# MAIN.net
KiCad netlist of a schematic drawn in Altium Designer
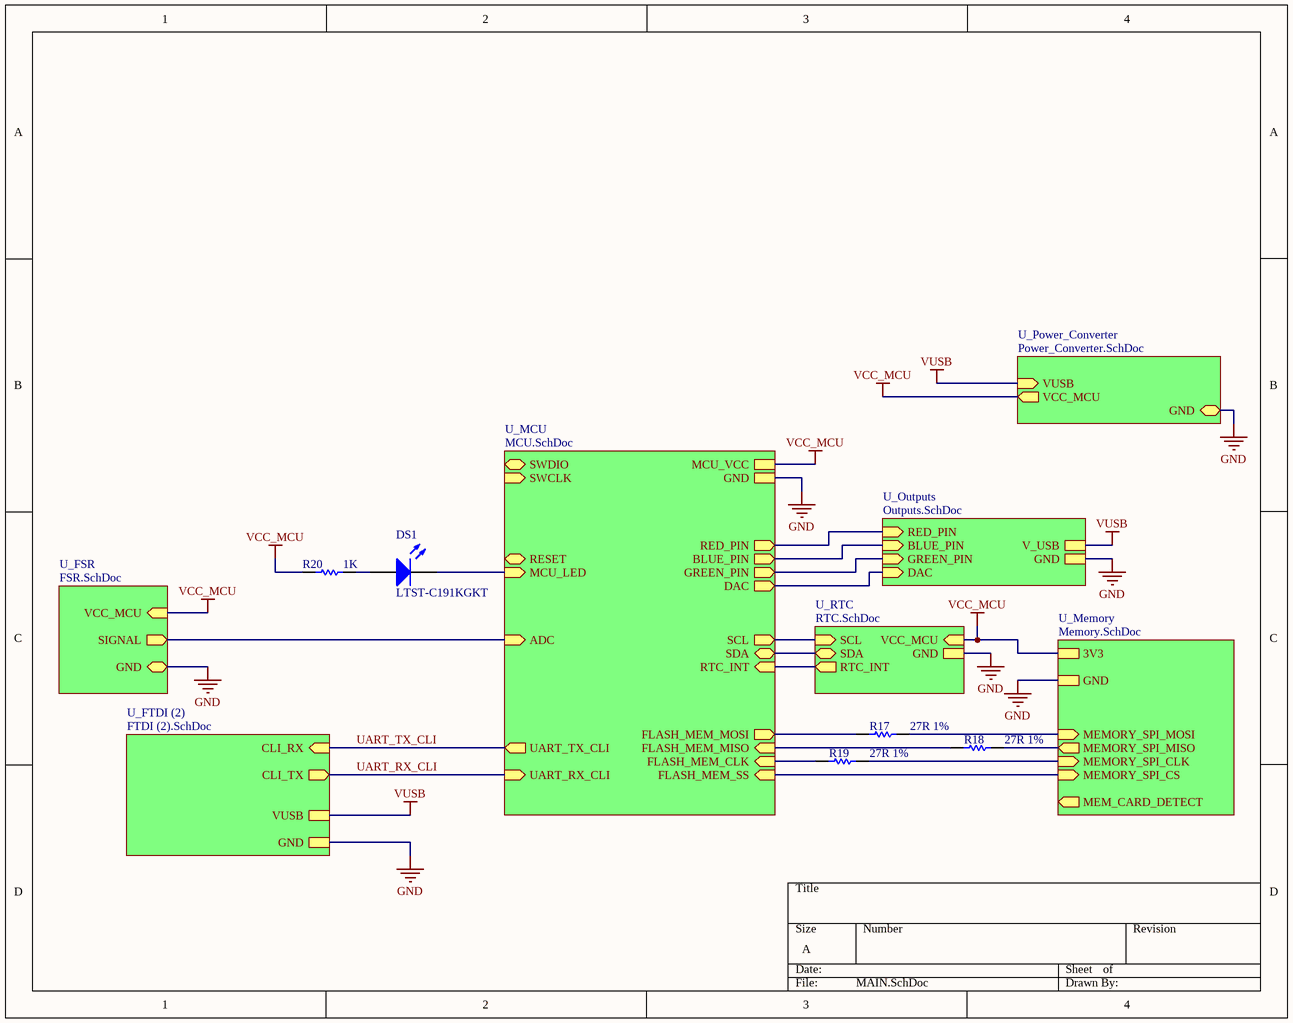
[diagram p0: MAIN.SchDoc]

(export (version "E")
  (design (tool "Eeschema 10.0.6"))
  (components
    (comp (ref "DS1")
      (value "LTST-C191KGKT")
      (footprint "LITE-ON-LTST-C191KRKT-2_V")
      (description "Chip LED, Green, 574 nm, 40 pF, -55 to 85 degC, 2-Pin SMD, RoHS, Tape and Reel")
      (fields (field (name "MANUFACTURER") "Lite-On"))
      (libsource (lib "Altium Content Vault") (part "LED-AK-2"))
    )
    (comp (ref "R17")
      (value "27R 1%")
      (footprint "RESC0603(1608)_N")
      (description "27R 0.1W 1% 0603 (1608 Metric)  SMD")
      (fields (field (name "TOLERANCE") "1 %") (field (name "POWER") "0.1 W"))
      (libsource (lib "Altium Content Vault") (part "RES"))
    )
    (comp (ref "R18")
      (value "27R 1%")
      (footprint "RESC0603(1608)_N")
      (description "27R 0.1W 1% 0603 (1608 Metric)  SMD")
      (fields (field (name "TOLERANCE") "1 %") (field (name "POWER") "0.1 W"))
      (libsource (lib "Altium Content Vault") (part "RES"))
    )
    (comp (ref "R19")
      (value "27R 1%")
      (footprint "RESC0603(1608)_N")
      (description "27R 0.1W 1% 0603 (1608 Metric)  SMD")
      (fields (field (name "TOLERANCE") "1 %") (field (name "POWER") "0.1 W"))
      (libsource (lib "Altium Content Vault") (part "RES"))
    )
    (comp (ref "R20")
      (value "1K")
      (footprint "RESC0603(1608)_M")
      (description "1K 0.1W 1% 0603 (1608 Metric)  SMD")
      (fields (field (name "TOLERANCE") "1 %") (field (name "POWER") "0.1 W"))
      (libsource (lib "Altium Content Vault") (part "RES"))
    )
  )
  (nets
    (net (code "3") (name "/FLASH_MEM_CLK") (class "Default")
      (node (ref "R19") (pin "1") (pinfunction "1_1") (pintype "passive"))
    )
    (net (code "4") (name "/FLASH_MEM_MISO") (class "Default")
      (node (ref "R18") (pin "1") (pinfunction "1_1") (pintype "passive"))
    )
    (net (code "5") (name "/FLASH_MEM_MOSI") (class "Default")
      (node (ref "R17") (pin "1") (pinfunction "1_1") (pintype "passive"))
    )
    (net (code "8") (name "/MCU_LED") (class "Default")
      (node (ref "DS1") (pin "2") (pinfunction "K_2") (pintype "passive"))
    )
    (net (code "9") (name "/MEMORY_SPI_CLK") (class "Default")
      (node (ref "R19") (pin "2") (pinfunction "2_2") (pintype "passive"))
    )
    (net (code "10") (name "/MEMORY_SPI_MISO") (class "Default")
      (node (ref "R18") (pin "2") (pinfunction "2_2") (pintype "passive"))
    )
    (net (code "11") (name "/MEMORY_SPI_MOSI") (class "Default")
      (node (ref "R17") (pin "2") (pinfunction "2_2") (pintype "passive"))
    )
    (net (code "24") (name "Net-(DS1-A)") (class "Default")
      (node (ref "DS1") (pin "1") (pinfunction "A_1") (pintype "passive"))
      (node (ref "R20") (pin "2") (pinfunction "2_2") (pintype "passive"))
    )
    (net (code "25") (name "VCC_MCU") (class "Default")
      (node (ref "R20") (pin "1") (pinfunction "1_1") (pintype "passive"))
    )
  )
)
